# PortExpander.net
KiCad netlist of a schematic drawn in EAGLE
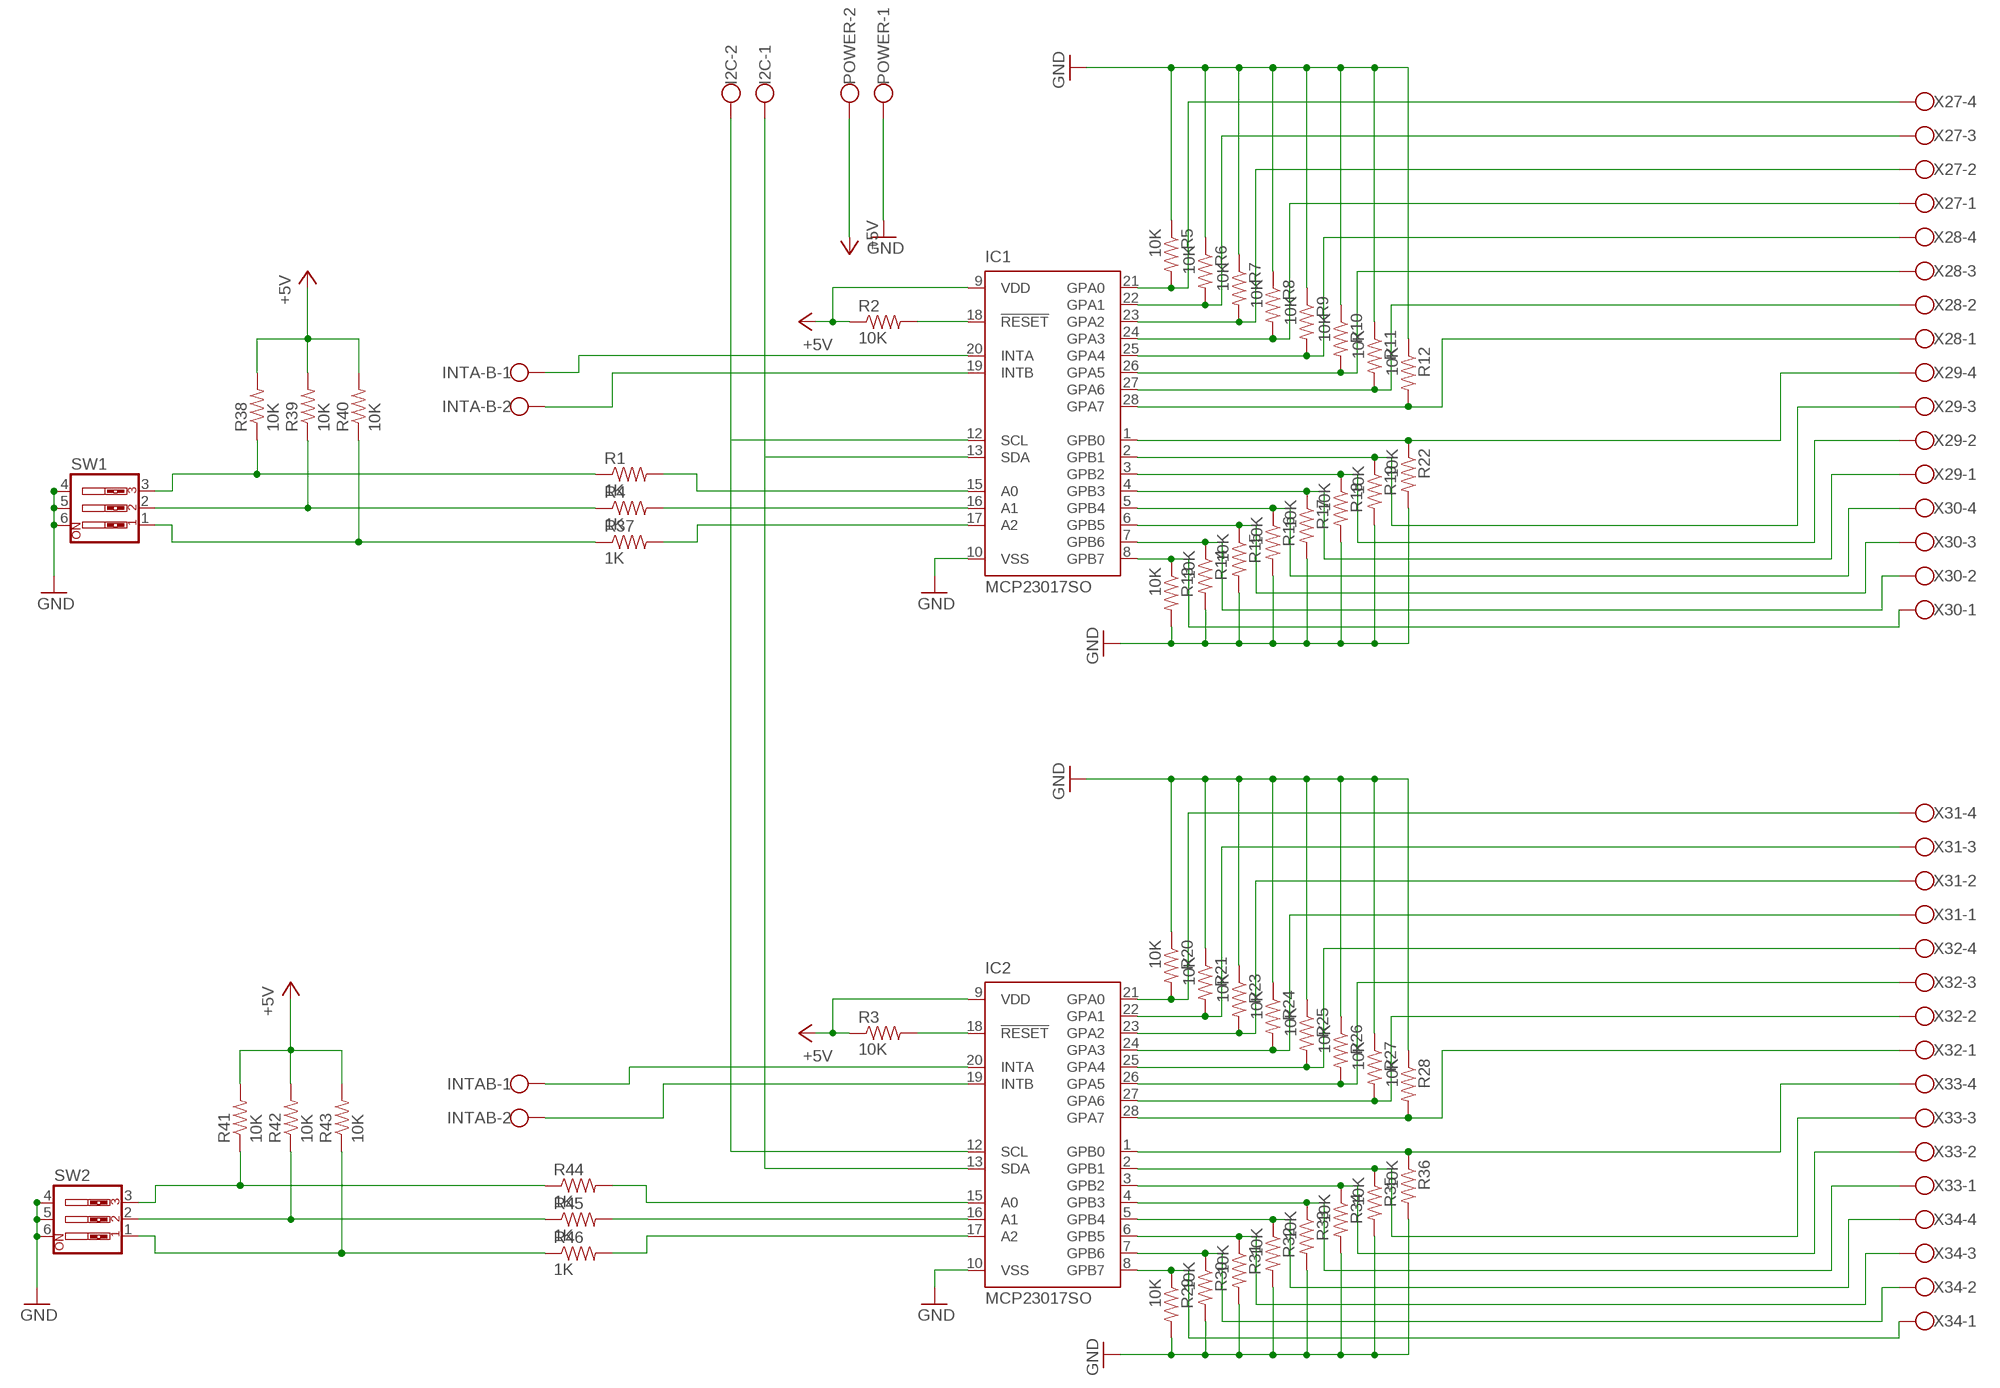
[diagram p0: schematic, sheet 1]

(export (version "E")
  (design (tool "Eeschema 10.0.6"))
  (components
    (comp (ref "I2C")
      (value "W237-102")
      (footprint "eagle-import:W237-102")
      (fields (field (name "MPN") "237-102"))
      (libsource (lib "eagle-import") (part "W237-102"))
    )
    (comp (ref "IC1")
      (value "MCP23017SO")
      (footprint "eagle-import:SO28W")
      (fields (field (name "MF") "MICROCHIP") (field (name "MPN") "MCP23017-E/SO"))
      (libsource (lib "eagle-import") (part "MCP23017SO"))
    )
    (comp (ref "IC2")
      (value "MCP23017SO")
      (footprint "eagle-import:SO28W")
      (fields (field (name "MF") "MICROCHIP") (field (name "MPN") "MCP23017-E/SO"))
      (libsource (lib "eagle-import") (part "MCP23017SO"))
    )
    (comp (ref "INTA-B")
      (value "W237-102")
      (footprint "eagle-import:W237-102")
      (fields (field (name "MPN") "237-102"))
      (libsource (lib "eagle-import") (part "W237-102"))
    )
    (comp (ref "INTAB")
      (value "W237-102")
      (footprint "eagle-import:W237-102")
      (fields (field (name "MPN") "237-102"))
      (libsource (lib "eagle-import") (part "W237-102"))
    )
    (comp (ref "POWER")
      (value "W237-102")
      (footprint "eagle-import:W237-102")
      (fields (field (name "MPN") "237-102"))
      (libsource (lib "eagle-import") (part "W237-102"))
    )
    (comp (ref "R1")
      (value "1K")
      (footprint "eagle-import:1206")
      (libsource (lib "eagle-import") (part "RESISTOR1206"))
    )
    (comp (ref "R2")
      (value "10K")
      (footprint "eagle-import:1206")
      (libsource (lib "eagle-import") (part "RESISTOR1206"))
    )
    (comp (ref "R3")
      (value "10K")
      (footprint "eagle-import:1206")
      (libsource (lib "eagle-import") (part "RESISTOR1206"))
    )
    (comp (ref "R4")
      (value "1K")
      (footprint "eagle-import:1206")
      (libsource (lib "eagle-import") (part "RESISTOR1206"))
    )
    (comp (ref "R5")
      (value "10K")
      (footprint "eagle-import:1206")
      (libsource (lib "eagle-import") (part "RESISTOR1206"))
    )
    (comp (ref "R6")
      (value "10K")
      (footprint "eagle-import:1206")
      (libsource (lib "eagle-import") (part "RESISTOR1206"))
    )
    (comp (ref "R7")
      (value "10K")
      (footprint "eagle-import:1206")
      (libsource (lib "eagle-import") (part "RESISTOR1206"))
    )
    (comp (ref "R8")
      (value "10K")
      (footprint "eagle-import:1206")
      (libsource (lib "eagle-import") (part "RESISTOR1206"))
    )
    (comp (ref "R9")
      (value "10K")
      (footprint "eagle-import:1206")
      (libsource (lib "eagle-import") (part "RESISTOR1206"))
    )
    (comp (ref "R10")
      (value "10K")
      (footprint "eagle-import:1206")
      (libsource (lib "eagle-import") (part "RESISTOR1206"))
    )
    (comp (ref "R11")
      (value "10K")
      (footprint "eagle-import:1206")
      (libsource (lib "eagle-import") (part "RESISTOR1206"))
    )
    (comp (ref "R12")
      (value "10K")
      (footprint "eagle-import:1206")
      (libsource (lib "eagle-import") (part "RESISTOR1206"))
    )
    (comp (ref "R13")
      (value "10K")
      (footprint "eagle-import:1206")
      (libsource (lib "eagle-import") (part "RESISTOR1206"))
    )
    (comp (ref "R14")
      (value "10K")
      (footprint "eagle-import:1206")
      (libsource (lib "eagle-import") (part "RESISTOR1206"))
    )
    (comp (ref "R15")
      (value "10K")
      (footprint "eagle-import:1206")
      (libsource (lib "eagle-import") (part "RESISTOR1206"))
    )
    (comp (ref "R16")
      (value "10K")
      (footprint "eagle-import:1206")
      (libsource (lib "eagle-import") (part "RESISTOR1206"))
    )
    (comp (ref "R17")
      (value "10K")
      (footprint "eagle-import:1206")
      (libsource (lib "eagle-import") (part "RESISTOR1206"))
    )
    (comp (ref "R18")
      (value "10K")
      (footprint "eagle-import:1206")
      (libsource (lib "eagle-import") (part "RESISTOR1206"))
    )
    (comp (ref "R19")
      (value "10K")
      (footprint "eagle-import:1206")
      (libsource (lib "eagle-import") (part "RESISTOR1206"))
    )
    (comp (ref "R20")
      (value "10K")
      (footprint "eagle-import:1206")
      (libsource (lib "eagle-import") (part "RESISTOR1206"))
    )
    (comp (ref "R21")
      (value "10K")
      (footprint "eagle-import:1206")
      (libsource (lib "eagle-import") (part "RESISTOR1206"))
    )
    (comp (ref "R22")
      (value "10K")
      (footprint "eagle-import:1206")
      (libsource (lib "eagle-import") (part "RESISTOR1206"))
    )
    (comp (ref "R23")
      (value "10K")
      (footprint "eagle-import:1206")
      (libsource (lib "eagle-import") (part "RESISTOR1206"))
    )
    (comp (ref "R24")
      (value "10K")
      (footprint "eagle-import:1206")
      (libsource (lib "eagle-import") (part "RESISTOR1206"))
    )
    (comp (ref "R25")
      (value "10K")
      (footprint "eagle-import:1206")
      (libsource (lib "eagle-import") (part "RESISTOR1206"))
    )
    (comp (ref "R26")
      (value "10K")
      (footprint "eagle-import:1206")
      (libsource (lib "eagle-import") (part "RESISTOR1206"))
    )
    (comp (ref "R27")
      (value "10K")
      (footprint "eagle-import:1206")
      (libsource (lib "eagle-import") (part "RESISTOR1206"))
    )
    (comp (ref "R28")
      (value "10K")
      (footprint "eagle-import:1206")
      (libsource (lib "eagle-import") (part "RESISTOR1206"))
    )
    (comp (ref "R29")
      (value "10K")
      (footprint "eagle-import:1206")
      (libsource (lib "eagle-import") (part "RESISTOR1206"))
    )
    (comp (ref "R30")
      (value "10K")
      (footprint "eagle-import:1206")
      (libsource (lib "eagle-import") (part "RESISTOR1206"))
    )
    (comp (ref "R31")
      (value "10K")
      (footprint "eagle-import:1206")
      (libsource (lib "eagle-import") (part "RESISTOR1206"))
    )
    (comp (ref "R32")
      (value "10K")
      (footprint "eagle-import:1206")
      (libsource (lib "eagle-import") (part "RESISTOR1206"))
    )
    (comp (ref "R33")
      (value "10K")
      (footprint "eagle-import:1206")
      (libsource (lib "eagle-import") (part "RESISTOR1206"))
    )
    (comp (ref "R34")
      (value "10K")
      (footprint "eagle-import:1206")
      (libsource (lib "eagle-import") (part "RESISTOR1206"))
    )
    (comp (ref "R35")
      (value "10K")
      (footprint "eagle-import:1206")
      (libsource (lib "eagle-import") (part "RESISTOR1206"))
    )
    (comp (ref "R36")
      (value "10K")
      (footprint "eagle-import:1206")
      (libsource (lib "eagle-import") (part "RESISTOR1206"))
    )
    (comp (ref "R37")
      (value "1K")
      (footprint "eagle-import:1206")
      (libsource (lib "eagle-import") (part "RESISTOR1206"))
    )
    (comp (ref "R38")
      (value "10K")
      (footprint "eagle-import:1206")
      (libsource (lib "eagle-import") (part "RESISTOR1206"))
    )
    (comp (ref "R39")
      (value "10K")
      (footprint "eagle-import:1206")
      (libsource (lib "eagle-import") (part "RESISTOR1206"))
    )
    (comp (ref "R40")
      (value "10K")
      (footprint "eagle-import:1206")
      (libsource (lib "eagle-import") (part "RESISTOR1206"))
    )
    (comp (ref "R41")
      (value "10K")
      (footprint "eagle-import:1206")
      (libsource (lib "eagle-import") (part "RESISTOR1206"))
    )
    (comp (ref "R42")
      (value "10K")
      (footprint "eagle-import:1206")
      (libsource (lib "eagle-import") (part "RESISTOR1206"))
    )
    (comp (ref "R43")
      (value "10K")
      (footprint "eagle-import:1206")
      (libsource (lib "eagle-import") (part "RESISTOR1206"))
    )
    (comp (ref "R44")
      (value "1K")
      (footprint "eagle-import:1206")
      (libsource (lib "eagle-import") (part "RESISTOR1206"))
    )
    (comp (ref "R45")
      (value "1K")
      (footprint "eagle-import:1206")
      (libsource (lib "eagle-import") (part "RESISTOR1206"))
    )
    (comp (ref "R46")
      (value "1K")
      (footprint "eagle-import:1206")
      (libsource (lib "eagle-import") (part "RESISTOR1206"))
    )
    (comp (ref "SW1")
      (value "SW_DIP-3")
      (footprint "eagle-import:EDG-03")
      (libsource (lib "eagle-import") (part "SW_DIP-3"))
    )
    (comp (ref "SW2")
      (value "SW_DIP-3")
      (footprint "eagle-import:EDG-03")
      (libsource (lib "eagle-import") (part "SW_DIP-3"))
    )
    (comp (ref "X27")
      (value "W237-4")
      (footprint "eagle-import:W237-4")
      (libsource (lib "eagle-import") (part "W237-4"))
    )
    (comp (ref "X28")
      (value "W237-4")
      (footprint "eagle-import:W237-4")
      (libsource (lib "eagle-import") (part "W237-4"))
    )
    (comp (ref "X29")
      (value "W237-4")
      (footprint "eagle-import:W237-4")
      (libsource (lib "eagle-import") (part "W237-4"))
    )
    (comp (ref "X30")
      (value "W237-4")
      (footprint "eagle-import:W237-4")
      (libsource (lib "eagle-import") (part "W237-4"))
    )
    (comp (ref "X31")
      (value "W237-4")
      (footprint "eagle-import:W237-4")
      (libsource (lib "eagle-import") (part "W237-4"))
    )
    (comp (ref "X32")
      (value "W237-4")
      (footprint "eagle-import:W237-4")
      (libsource (lib "eagle-import") (part "W237-4"))
    )
    (comp (ref "X33")
      (value "W237-4")
      (footprint "eagle-import:W237-4")
      (libsource (lib "eagle-import") (part "W237-4"))
    )
    (comp (ref "X34")
      (value "W237-4")
      (footprint "eagle-import:W237-4")
      (libsource (lib "eagle-import") (part "W237-4"))
    )
  )
  (nets
    (net (code "1") (name "+5V") (class "Default")
      (node (ref "IC1") (pin "9") (pinfunction "VDD_9") (pintype "power_in"))
      (node (ref "IC2") (pin "9") (pinfunction "VDD_9") (pintype "power_in"))
      (node (ref "POWER") (pin "2") (pinfunction "KL_2") (pintype "passive"))
      (node (ref "R2") (pin "1") (pinfunction "1_1") (pintype "passive"))
      (node (ref "R3") (pin "1") (pinfunction "1_1") (pintype "passive"))
      (node (ref "R38") (pin "2") (pinfunction "2_2") (pintype "passive"))
      (node (ref "R39") (pin "2") (pinfunction "2_2") (pintype "passive"))
      (node (ref "R40") (pin "2") (pinfunction "2_2") (pintype "passive"))
      (node (ref "R41") (pin "2") (pinfunction "2_2") (pintype "passive"))
      (node (ref "R42") (pin "2") (pinfunction "2_2") (pintype "passive"))
      (node (ref "R43") (pin "2") (pinfunction "2_2") (pintype "passive"))
    )
    (net (code "2") (name "GND") (class "Default")
      (node (ref "IC1") (pin "10") (pinfunction "VSS_10") (pintype "power_in"))
      (node (ref "IC2") (pin "10") (pinfunction "VSS_10") (pintype "power_in"))
      (node (ref "POWER") (pin "1") (pinfunction "KL_1") (pintype "passive"))
      (node (ref "R10") (pin "1") (pinfunction "1_1") (pintype "passive"))
      (node (ref "R11") (pin "1") (pinfunction "1_1") (pintype "passive"))
      (node (ref "R12") (pin "1") (pinfunction "1_1") (pintype "passive"))
      (node (ref "R13") (pin "2") (pinfunction "2_2") (pintype "passive"))
      (node (ref "R14") (pin "2") (pinfunction "2_2") (pintype "passive"))
      (node (ref "R15") (pin "2") (pinfunction "2_2") (pintype "passive"))
      (node (ref "R16") (pin "2") (pinfunction "2_2") (pintype "passive"))
      (node (ref "R17") (pin "2") (pinfunction "2_2") (pintype "passive"))
      (node (ref "R18") (pin "2") (pinfunction "2_2") (pintype "passive"))
      (node (ref "R19") (pin "2") (pinfunction "2_2") (pintype "passive"))
      (node (ref "R20") (pin "1") (pinfunction "1_1") (pintype "passive"))
      (node (ref "R21") (pin "1") (pinfunction "1_1") (pintype "passive"))
      (node (ref "R22") (pin "2") (pinfunction "2_2") (pintype "passive"))
      (node (ref "R23") (pin "1") (pinfunction "1_1") (pintype "passive"))
      (node (ref "R24") (pin "1") (pinfunction "1_1") (pintype "passive"))
      (node (ref "R25") (pin "1") (pinfunction "1_1") (pintype "passive"))
      (node (ref "R26") (pin "1") (pinfunction "1_1") (pintype "passive"))
      (node (ref "R27") (pin "1") (pinfunction "1_1") (pintype "passive"))
      (node (ref "R28") (pin "1") (pinfunction "1_1") (pintype "passive"))
      (node (ref "R29") (pin "2") (pinfunction "2_2") (pintype "passive"))
      (node (ref "R30") (pin "2") (pinfunction "2_2") (pintype "passive"))
      (node (ref "R31") (pin "2") (pinfunction "2_2") (pintype "passive"))
      (node (ref "R32") (pin "2") (pinfunction "2_2") (pintype "passive"))
      (node (ref "R33") (pin "2") (pinfunction "2_2") (pintype "passive"))
      (node (ref "R34") (pin "2") (pinfunction "2_2") (pintype "passive"))
      (node (ref "R35") (pin "2") (pinfunction "2_2") (pintype "passive"))
      (node (ref "R36") (pin "2") (pinfunction "2_2") (pintype "passive"))
      (node (ref "R5") (pin "1") (pinfunction "1_1") (pintype "passive"))
      (node (ref "R6") (pin "1") (pinfunction "1_1") (pintype "passive"))
      (node (ref "R7") (pin "1") (pinfunction "1_1") (pintype "passive"))
      (node (ref "R8") (pin "1") (pinfunction "1_1") (pintype "passive"))
      (node (ref "R9") (pin "1") (pinfunction "1_1") (pintype "passive"))
      (node (ref "SW1") (pin "4") (pinfunction "4_4") (pintype "passive"))
      (node (ref "SW1") (pin "5") (pinfunction "5_5") (pintype "passive"))
      (node (ref "SW1") (pin "6") (pinfunction "6_6") (pintype "passive"))
      (node (ref "SW2") (pin "4") (pinfunction "4_4") (pintype "passive"))
      (node (ref "SW2") (pin "5") (pinfunction "5_5") (pintype "passive"))
      (node (ref "SW2") (pin "6") (pinfunction "6_6") (pintype "passive"))
    )
    (net (code "3") (name "Net-(I2CA-KL)") (class "Default")
      (node (ref "I2C") (pin "1") (pinfunction "KL_1") (pintype "passive"))
      (node (ref "IC1") (pin "13") (pinfunction "SDA_13") (pintype "bidirectional"))
      (node (ref "IC2") (pin "13") (pinfunction "SDA_13") (pintype "bidirectional"))
    )
    (net (code "4") (name "Net-(I2CB-KL)") (class "Default")
      (node (ref "I2C") (pin "2") (pinfunction "KL_2") (pintype "passive"))
      (node (ref "IC1") (pin "12") (pinfunction "SCL_12") (pintype "input"))
      (node (ref "IC2") (pin "12") (pinfunction "SCL_12") (pintype "input"))
    )
    (net (code "5") (name "Net-(IC1-A0)") (class "Default")
      (node (ref "IC1") (pin "15") (pinfunction "A0_15") (pintype "input"))
      (node (ref "R1") (pin "2") (pinfunction "2_2") (pintype "passive"))
    )
    (net (code "6") (name "Net-(IC1-A1)") (class "Default")
      (node (ref "IC1") (pin "16") (pinfunction "A1_16") (pintype "input"))
      (node (ref "R4") (pin "2") (pinfunction "2_2") (pintype "passive"))
    )
    (net (code "7") (name "Net-(IC1-A2)") (class "Default")
      (node (ref "IC1") (pin "17") (pinfunction "A2_17") (pintype "input"))
      (node (ref "R37") (pin "2") (pinfunction "2_2") (pintype "passive"))
    )
    (net (code "8") (name "Net-(IC1-GPA0)") (class "Default")
      (node (ref "IC1") (pin "21") (pinfunction "GPA0_21") (pintype "bidirectional"))
      (node (ref "R5") (pin "2") (pinfunction "2_2") (pintype "passive"))
      (node (ref "X27") (pin "4") (pinfunction "KL_4") (pintype "passive"))
    )
    (net (code "9") (name "Net-(IC1-GPA1)") (class "Default")
      (node (ref "IC1") (pin "22") (pinfunction "GPA1_22") (pintype "bidirectional"))
      (node (ref "R6") (pin "2") (pinfunction "2_2") (pintype "passive"))
      (node (ref "X27") (pin "3") (pinfunction "KL_3") (pintype "passive"))
    )
    (net (code "10") (name "Net-(IC1-GPA2)") (class "Default")
      (node (ref "IC1") (pin "23") (pinfunction "GPA2_23") (pintype "bidirectional"))
      (node (ref "R7") (pin "2") (pinfunction "2_2") (pintype "passive"))
      (node (ref "X27") (pin "2") (pinfunction "KL_2") (pintype "passive"))
    )
    (net (code "11") (name "Net-(IC1-GPA3)") (class "Default")
      (node (ref "IC1") (pin "24") (pinfunction "GPA3_24") (pintype "bidirectional"))
      (node (ref "R8") (pin "2") (pinfunction "2_2") (pintype "passive"))
      (node (ref "X27") (pin "1") (pinfunction "KL_1") (pintype "passive"))
    )
    (net (code "12") (name "Net-(IC1-GPA4)") (class "Default")
      (node (ref "IC1") (pin "25") (pinfunction "GPA4_25") (pintype "bidirectional"))
      (node (ref "R9") (pin "2") (pinfunction "2_2") (pintype "passive"))
      (node (ref "X28") (pin "4") (pinfunction "KL_4") (pintype "passive"))
    )
    (net (code "13") (name "Net-(IC1-GPA5)") (class "Default")
      (node (ref "IC1") (pin "26") (pinfunction "GPA5_26") (pintype "bidirectional"))
      (node (ref "R10") (pin "2") (pinfunction "2_2") (pintype "passive"))
      (node (ref "X28") (pin "3") (pinfunction "KL_3") (pintype "passive"))
    )
    (net (code "14") (name "Net-(IC1-GPA6)") (class "Default")
      (node (ref "IC1") (pin "27") (pinfunction "GPA6_27") (pintype "bidirectional"))
      (node (ref "R11") (pin "2") (pinfunction "2_2") (pintype "passive"))
      (node (ref "X28") (pin "2") (pinfunction "KL_2") (pintype "passive"))
    )
    (net (code "15") (name "Net-(IC1-GPA7)") (class "Default")
      (node (ref "IC1") (pin "28") (pinfunction "GPA7_28") (pintype "bidirectional"))
      (node (ref "R12") (pin "2") (pinfunction "2_2") (pintype "passive"))
      (node (ref "X28") (pin "1") (pinfunction "KL_1") (pintype "passive"))
    )
    (net (code "16") (name "Net-(IC1-GPB0)") (class "Default")
      (node (ref "IC1") (pin "1") (pinfunction "GPB0_1") (pintype "bidirectional"))
      (node (ref "R22") (pin "1") (pinfunction "1_1") (pintype "passive"))
      (node (ref "X29") (pin "4") (pinfunction "KL_4") (pintype "passive"))
    )
    (net (code "17") (name "Net-(IC1-GPB1)") (class "Default")
      (node (ref "IC1") (pin "2") (pinfunction "GPB1_2") (pintype "bidirectional"))
      (node (ref "R19") (pin "1") (pinfunction "1_1") (pintype "passive"))
      (node (ref "X29") (pin "3") (pinfunction "KL_3") (pintype "passive"))
    )
    (net (code "18") (name "Net-(IC1-GPB2)") (class "Default")
      (node (ref "IC1") (pin "3") (pinfunction "GPB2_3") (pintype "bidirectional"))
      (node (ref "R18") (pin "1") (pinfunction "1_1") (pintype "passive"))
      (node (ref "X29") (pin "2") (pinfunction "KL_2") (pintype "passive"))
    )
    (net (code "19") (name "Net-(IC1-GPB3)") (class "Default")
      (node (ref "IC1") (pin "4") (pinfunction "GPB3_4") (pintype "bidirectional"))
      (node (ref "R17") (pin "1") (pinfunction "1_1") (pintype "passive"))
      (node (ref "X29") (pin "1") (pinfunction "KL_1") (pintype "passive"))
    )
    (net (code "20") (name "Net-(IC1-GPB4)") (class "Default")
      (node (ref "IC1") (pin "5") (pinfunction "GPB4_5") (pintype "bidirectional"))
      (node (ref "R16") (pin "1") (pinfunction "1_1") (pintype "passive"))
      (node (ref "X30") (pin "4") (pinfunction "KL_4") (pintype "passive"))
    )
    (net (code "21") (name "Net-(IC1-GPB5)") (class "Default")
      (node (ref "IC1") (pin "6") (pinfunction "GPB5_6") (pintype "bidirectional"))
      (node (ref "R15") (pin "1") (pinfunction "1_1") (pintype "passive"))
      (node (ref "X30") (pin "3") (pinfunction "KL_3") (pintype "passive"))
    )
    (net (code "22") (name "Net-(IC1-GPB6)") (class "Default")
      (node (ref "IC1") (pin "7") (pinfunction "GPB6_7") (pintype "bidirectional"))
      (node (ref "R14") (pin "1") (pinfunction "1_1") (pintype "passive"))
      (node (ref "X30") (pin "2") (pinfunction "KL_2") (pintype "passive"))
    )
    (net (code "23") (name "Net-(IC1-GPB7)") (class "Default")
      (node (ref "IC1") (pin "8") (pinfunction "GPB7_8") (pintype "bidirectional"))
      (node (ref "R13") (pin "1") (pinfunction "1_1") (pintype "passive"))
      (node (ref "X30") (pin "1") (pinfunction "KL_1") (pintype "passive"))
    )
    (net (code "24") (name "Net-(IC1-INTA)") (class "Default")
      (node (ref "IC1") (pin "20") (pinfunction "INTA_20") (pintype "output"))
      (node (ref "INTA-B") (pin "1") (pinfunction "KL_1") (pintype "passive"))
    )
    (net (code "25") (name "Net-(IC1-INTB)") (class "Default")
      (node (ref "IC1") (pin "19") (pinfunction "INTB_19") (pintype "output"))
      (node (ref "INTA-B") (pin "2") (pinfunction "KL_2") (pintype "passive"))
    )
    (net (code "26") (name "Net-(IC1-~{RESET})") (class "Default")
      (node (ref "IC1") (pin "18") (pinfunction "~{RESET}_18") (pintype "input"))
      (node (ref "R2") (pin "2") (pinfunction "2_2") (pintype "passive"))
    )
    (net (code "27") (name "Net-(IC2-A0)") (class "Default")
      (node (ref "IC2") (pin "15") (pinfunction "A0_15") (pintype "input"))
      (node (ref "R44") (pin "2") (pinfunction "2_2") (pintype "passive"))
    )
    (net (code "28") (name "Net-(IC2-A1)") (class "Default")
      (node (ref "IC2") (pin "16") (pinfunction "A1_16") (pintype "input"))
      (node (ref "R45") (pin "2") (pinfunction "2_2") (pintype "passive"))
    )
    (net (code "29") (name "Net-(IC2-A2)") (class "Default")
      (node (ref "IC2") (pin "17") (pinfunction "A2_17") (pintype "input"))
      (node (ref "R46") (pin "2") (pinfunction "2_2") (pintype "passive"))
    )
    (net (code "30") (name "Net-(IC2-GPA0)") (class "Default")
      (node (ref "IC2") (pin "21") (pinfunction "GPA0_21") (pintype "bidirectional"))
      (node (ref "R20") (pin "2") (pinfunction "2_2") (pintype "passive"))
      (node (ref "X31") (pin "4") (pinfunction "KL_4") (pintype "passive"))
    )
    (net (code "31") (name "Net-(IC2-GPA1)") (class "Default")
      (node (ref "IC2") (pin "22") (pinfunction "GPA1_22") (pintype "bidirectional"))
      (node (ref "R21") (pin "2") (pinfunction "2_2") (pintype "passive"))
      (node (ref "X31") (pin "3") (pinfunction "KL_3") (pintype "passive"))
    )
    (net (code "32") (name "Net-(IC2-GPA2)") (class "Default")
      (node (ref "IC2") (pin "23") (pinfunction "GPA2_23") (pintype "bidirectional"))
      (node (ref "R23") (pin "2") (pinfunction "2_2") (pintype "passive"))
      (node (ref "X31") (pin "2") (pinfunction "KL_2") (pintype "passive"))
    )
    (net (code "33") (name "Net-(IC2-GPA3)") (class "Default")
      (node (ref "IC2") (pin "24") (pinfunction "GPA3_24") (pintype "bidirectional"))
      (node (ref "R24") (pin "2") (pinfunction "2_2") (pintype "passive"))
      (node (ref "X31") (pin "1") (pinfunction "KL_1") (pintype "passive"))
    )
    (net (code "34") (name "Net-(IC2-GPA4)") (class "Default")
      (node (ref "IC2") (pin "25") (pinfunction "GPA4_25") (pintype "bidirectional"))
      (node (ref "R25") (pin "2") (pinfunction "2_2") (pintype "passive"))
      (node (ref "X32") (pin "4") (pinfunction "KL_4") (pintype "passive"))
    )
    (net (code "35") (name "Net-(IC2-GPA5)") (class "Default")
      (node (ref "IC2") (pin "26") (pinfunction "GPA5_26") (pintype "bidirectional"))
      (node (ref "R26") (pin "2") (pinfunction "2_2") (pintype "passive"))
      (node (ref "X32") (pin "3") (pinfunction "KL_3") (pintype "passive"))
    )
    (net (code "36") (name "Net-(IC2-GPA6)") (class "Default")
      (node (ref "IC2") (pin "27") (pinfunction "GPA6_27") (pintype "bidirectional"))
      (node (ref "R27") (pin "2") (pinfunction "2_2") (pintype "passive"))
      (node (ref "X32") (pin "2") (pinfunction "KL_2") (pintype "passive"))
    )
    (net (code "37") (name "Net-(IC2-GPA7)") (class "Default")
      (node (ref "IC2") (pin "28") (pinfunction "GPA7_28") (pintype "bidirectional"))
      (node (ref "R28") (pin "2") (pinfunction "2_2") (pintype "passive"))
      (node (ref "X32") (pin "1") (pinfunction "KL_1") (pintype "passive"))
    )
    (net (code "38") (name "Net-(IC2-GPB0)") (class "Default")
      (node (ref "IC2") (pin "1") (pinfunction "GPB0_1") (pintype "bidirectional"))
      (node (ref "R36") (pin "1") (pinfunction "1_1") (pintype "passive"))
      (node (ref "X33") (pin "4") (pinfunction "KL_4") (pintype "passive"))
    )
    (net (code "39") (name "Net-(IC2-GPB1)") (class "Default")
      (node (ref "IC2") (pin "2") (pinfunction "GPB1_2") (pintype "bidirectional"))
      (node (ref "R35") (pin "1") (pinfunction "1_1") (pintype "passive"))
      (node (ref "X33") (pin "3") (pinfunction "KL_3") (pintype "passive"))
    )
    (net (code "40") (name "Net-(IC2-GPB2)") (class "Default")
      (node (ref "IC2") (pin "3") (pinfunction "GPB2_3") (pintype "bidirectional"))
      (node (ref "R34") (pin "1") (pinfunction "1_1") (pintype "passive"))
      (node (ref "X33") (pin "2") (pinfunction "KL_2") (pintype "passive"))
    )
    (net (code "41") (name "Net-(IC2-GPB3)") (class "Default")
      (node (ref "IC2") (pin "4") (pinfunction "GPB3_4") (pintype "bidirectional"))
      (node (ref "R33") (pin "1") (pinfunction "1_1") (pintype "passive"))
      (node (ref "X33") (pin "1") (pinfunction "KL_1") (pintype "passive"))
    )
    (net (code "42") (name "Net-(IC2-GPB4)") (class "Default")
      (node (ref "IC2") (pin "5") (pinfunction "GPB4_5") (pintype "bidirectional"))
      (node (ref "R32") (pin "1") (pinfunction "1_1") (pintype "passive"))
      (node (ref "X34") (pin "4") (pinfunction "KL_4") (pintype "passive"))
    )
    (net (code "43") (name "Net-(IC2-GPB5)") (class "Default")
      (node (ref "IC2") (pin "6") (pinfunction "GPB5_6") (pintype "bidirectional"))
      (node (ref "R31") (pin "1") (pinfunction "1_1") (pintype "passive"))
      (node (ref "X34") (pin "3") (pinfunction "KL_3") (pintype "passive"))
    )
    (net (code "44") (name "Net-(IC2-GPB6)") (class "Default")
      (node (ref "IC2") (pin "7") (pinfunction "GPB6_7") (pintype "bidirectional"))
      (node (ref "R30") (pin "1") (pinfunction "1_1") (pintype "passive"))
      (node (ref "X34") (pin "2") (pinfunction "KL_2") (pintype "passive"))
    )
    (net (code "45") (name "Net-(IC2-GPB7)") (class "Default")
      (node (ref "IC2") (pin "8") (pinfunction "GPB7_8") (pintype "bidirectional"))
      (node (ref "R29") (pin "1") (pinfunction "1_1") (pintype "passive"))
      (node (ref "X34") (pin "1") (pinfunction "KL_1") (pintype "passive"))
    )
    (net (code "46") (name "Net-(IC2-INTA)") (class "Default")
      (node (ref "IC2") (pin "20") (pinfunction "INTA_20") (pintype "output"))
      (node (ref "INTAB") (pin "1") (pinfunction "KL_1") (pintype "passive"))
    )
    (net (code "47") (name "Net-(IC2-INTB)") (class "Default")
      (node (ref "IC2") (pin "19") (pinfunction "INTB_19") (pintype "output"))
      (node (ref "INTAB") (pin "2") (pinfunction "KL_2") (pintype "passive"))
    )
    (net (code "48") (name "Net-(IC2-~{RESET})") (class "Default")
      (node (ref "IC2") (pin "18") (pinfunction "~{RESET}_18") (pintype "input"))
      (node (ref "R3") (pin "2") (pinfunction "2_2") (pintype "passive"))
    )
    (net (code "49") (name "Net-(R1-Pad1)") (class "Default")
      (node (ref "R1") (pin "1") (pinfunction "1_1") (pintype "passive"))
      (node (ref "R38") (pin "1") (pinfunction "1_1") (pintype "passive"))
      (node (ref "SW1") (pin "3") (pinfunction "3_3") (pintype "passive"))
    )
    (net (code "50") (name "Net-(R37-Pad1)") (class "Default")
      (node (ref "R37") (pin "1") (pinfunction "1_1") (pintype "passive"))
      (node (ref "R40") (pin "1") (pinfunction "1_1") (pintype "passive"))
      (node (ref "SW1") (pin "1") (pinfunction "1_1") (pintype "passive"))
    )
    (net (code "51") (name "Net-(R39-Pad1)") (class "Default")
      (node (ref "R39") (pin "1") (pinfunction "1_1") (pintype "passive"))
      (node (ref "R4") (pin "1") (pinfunction "1_1") (pintype "passive"))
      (node (ref "SW1") (pin "2") (pinfunction "2_2") (pintype "passive"))
    )
    (net (code "52") (name "Net-(R41-Pad1)") (class "Default")
      (node (ref "R41") (pin "1") (pinfunction "1_1") (pintype "passive"))
      (node (ref "R44") (pin "1") (pinfunction "1_1") (pintype "passive"))
      (node (ref "SW2") (pin "3") (pinfunction "3_3") (pintype "passive"))
    )
    (net (code "53") (name "Net-(R42-Pad1)") (class "Default")
      (node (ref "R42") (pin "1") (pinfunction "1_1") (pintype "passive"))
      (node (ref "R45") (pin "1") (pinfunction "1_1") (pintype "passive"))
      (node (ref "SW2") (pin "2") (pinfunction "2_2") (pintype "passive"))
    )
    (net (code "54") (name "Net-(R43-Pad1)") (class "Default")
      (node (ref "R43") (pin "1") (pinfunction "1_1") (pintype "passive"))
      (node (ref "R46") (pin "1") (pinfunction "1_1") (pintype "passive"))
      (node (ref "SW2") (pin "1") (pinfunction "1_1") (pintype "passive"))
    )
  )
)
